# dispay.net
KiCad netlist of a schematic drawn in Altium Designer
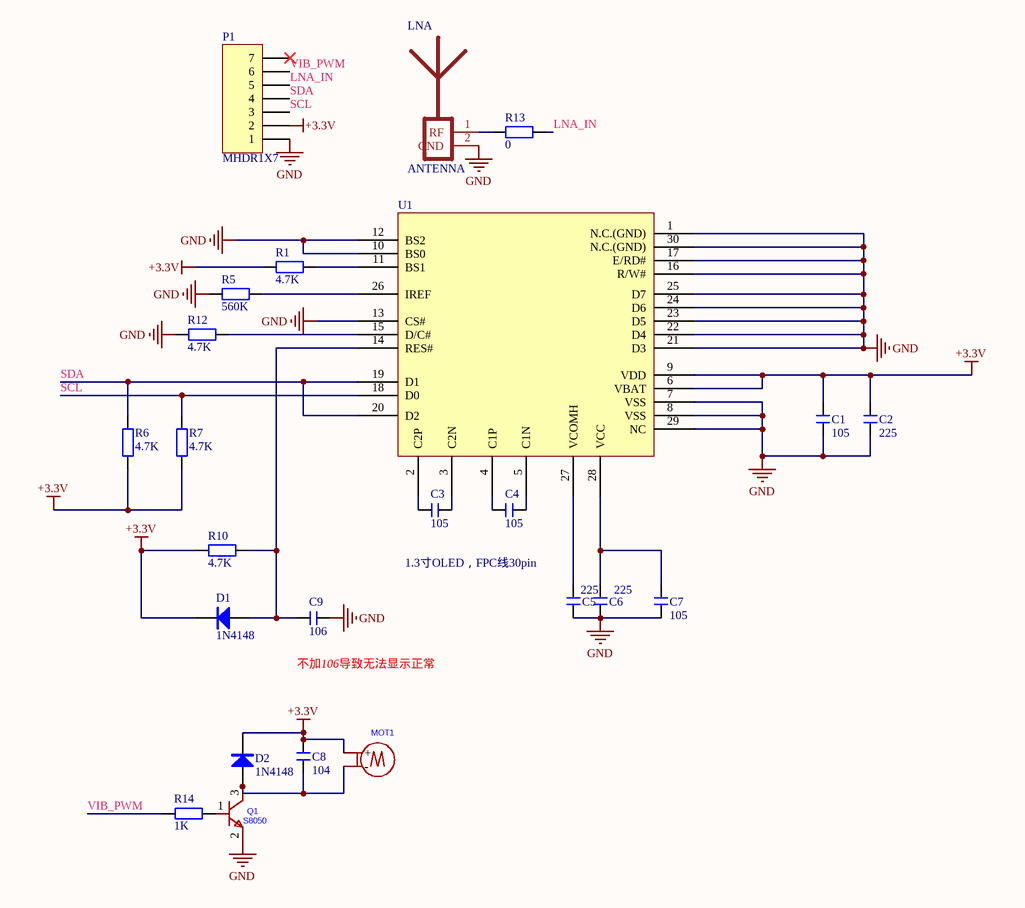
[diagram p0: dispay.SchDoc]

(export (version "E")
  (design (tool "Eeschema 10.0.6"))
  (components
    (comp (ref "C1")
      (value "105")
      (footprint "C0402-min")
      (description "无极性贴片电容")
      (fields (field (name "版权归属") "源创客"))
      (libsource (lib "3.1   - 电阻-电容-电感") (part "C"))
    )
    (comp (ref "C2")
      (value "225")
      (footprint "C0402-min")
      (description "无极性贴片电容")
      (fields (field (name "版权归属") "源创客"))
      (libsource (lib "3.1   - 电阻-电容-电感") (part "C"))
    )
    (comp (ref "C3")
      (value "105")
      (footprint "C0402-min")
      (description "无极性贴片电容")
      (fields (field (name "版权归属") "源创客"))
      (libsource (lib "3.1   - 电阻-电容-电感") (part "C"))
    )
    (comp (ref "C4")
      (value "105")
      (footprint "C0402-min")
      (description "无极性贴片电容")
      (fields (field (name "版权归属") "源创客"))
      (libsource (lib "3.1   - 电阻-电容-电感") (part "C"))
    )
    (comp (ref "C5")
      (value "225")
      (footprint "C0402-min")
      (description "无极性贴片电容")
      (fields (field (name "版权归属") "源创客"))
      (libsource (lib "3.1   - 电阻-电容-电感") (part "C"))
    )
    (comp (ref "C6")
      (value "225")
      (footprint "C0402-min")
      (description "无极性贴片电容")
      (fields (field (name "版权归属") "源创客"))
      (libsource (lib "3.1   - 电阻-电容-电感") (part "C"))
    )
    (comp (ref "C7")
      (value "105")
      (footprint "C0402-min")
      (description "无极性贴片电容")
      (fields (field (name "版权归属") "源创客"))
      (libsource (lib "3.1   - 电阻-电容-电感") (part "C"))
    )
    (comp (ref "C8")
      (value "104")
      (footprint "C0402-min")
      (description "无极性贴片电容")
      (fields (field (name "版权归属") "源创客"))
      (libsource (lib "3.1   - 电阻-电容-电感") (part "C"))
    )
    (comp (ref "C9")
      (value "106")
      (footprint "C0402-min")
      (description "无极性贴片电容")
      (fields (field (name "版权归属") "源创客"))
      (libsource (lib "3.1   - 电阻-电容-电感") (part "C"))
    )
    (comp (ref "D1")
      (value "1N4148")
      (footprint "SOD-323")
      (description "高速开关二极管")
      (fields (field (name "版权归属") "源创客"))
      (libsource (lib "8.1   - 二极管-整流桥") (part "1N4148"))
    )
    (comp (ref "D2")
      (value "1N4148")
      (footprint "SOD-323")
      (description "高速开关二极管")
      (fields (field (name "版权归属") "源创客"))
      (libsource (lib "8.1   - 二极管-整流桥") (part "1N4148"))
    )
    (comp (ref "LNA")
      (value "ANTENNA")
      (footprint "SWRA117D")
      (libsource (lib "Schlib-drive") (part "ANTENNA"))
    )
    (comp (ref "MOT1")
      (value "LCM1027A2445F")
      (footprint "Vibration_Motor0820")
      (fields (field (name "MANUFACTURER") "LEADER(立得)"))
      (libsource (lib "drive") (part "Vibration_Motor"))
    )
    (comp (ref "P1")
      (value "MHDR1X7")
      (footprint "MHDR1X7")
      (description "Header, 7-Pin")
      (fields (field (name "PUBLISHER") "Altium Limited"))
      (libsource (lib "Miscellaneous Connectors") (part "MHDR1X7"))
    )
    (comp (ref "Q1")
      (value "S8050")
      (footprint "SOT-23-3")
      (fields (field (name "MANUFACTURER") "宏嘉诚"))
      (libsource (lib "drive") (part "S8050"))
    )
    (comp (ref "R1")
      (value "4.7K")
      (footprint "R0402")
      (description "贴片电阻")
      (fields (field (name "版权归属") "源创客"))
      (libsource (lib "3.1   - 电阻-电容-电感") (part "R"))
    )
    (comp (ref "R5")
      (value "560K")
      (footprint "R0402")
      (description "贴片电阻")
      (fields (field (name "版权归属") "源创客"))
      (libsource (lib "3.1   - 电阻-电容-电感") (part "R"))
    )
    (comp (ref "R6")
      (value "4.7K")
      (footprint "R0402")
      (description "贴片电阻")
      (fields (field (name "版权归属") "源创客"))
      (libsource (lib "3.1   - 电阻-电容-电感") (part "R"))
    )
    (comp (ref "R7")
      (value "4.7K")
      (footprint "R0402")
      (description "贴片电阻")
      (fields (field (name "版权归属") "源创客"))
      (libsource (lib "3.1   - 电阻-电容-电感") (part "R"))
    )
    (comp (ref "R10")
      (value "4.7K")
      (footprint "R0402")
      (description "贴片电阻")
      (fields (field (name "版权归属") "源创客"))
      (libsource (lib "3.1   - 电阻-电容-电感") (part "R"))
    )
    (comp (ref "R12")
      (value "4.7K")
      (footprint "R0402")
      (description "贴片电阻")
      (fields (field (name "版权归属") "源创客"))
      (libsource (lib "3.1   - 电阻-电容-电感") (part "R"))
    )
    (comp (ref "R13")
      (value "0")
      (footprint "R0402")
      (description "贴片电阻")
      (fields (field (name "版权归属") "源创客"))
      (libsource (lib "3.1   - 电阻-电容-电感") (part "R"))
    )
    (comp (ref "R14")
      (value "1K")
      (footprint "R0402")
      (description "贴片电阻")
      (fields (field (name "版权归属") "源创客"))
      (libsource (lib "3.1   - 电阻-电容-电感") (part "R"))
    )
    (comp (ref "U1")
      (value "1.3寸OLED，FPC线30pin")
      (footprint "0.96OLED")
      (libsource (lib "我的元件") (part "1.3寸OLED，FPC线30pin"))
    )
  )
  (nets
    (net (code "1") (name "+3.3V") (class "Default")
      (node (ref "C1") (pin "2") (pinfunction "2_2") (pintype "passive"))
      (node (ref "C2") (pin "2") (pinfunction "2_2") (pintype "passive"))
      (node (ref "C8") (pin "2") (pinfunction "2_2") (pintype "passive"))
      (node (ref "D1") (pin "2") (pinfunction "K_2") (pintype "passive"))
      (node (ref "D2") (pin "2") (pinfunction "K_2") (pintype "passive"))
      (node (ref "MOT1") (pin "2") (pinfunction "+_2") (pintype "passive"))
      (node (ref "P1") (pin "2") (pinfunction "2_2") (pintype "passive"))
      (node (ref "R1") (pin "1") (pinfunction "1_1") (pintype "passive"))
      (node (ref "R10") (pin "1") (pinfunction "1_1") (pintype "passive"))
      (node (ref "R6") (pin "1") (pinfunction "1_1") (pintype "passive"))
      (node (ref "R7") (pin "1") (pinfunction "1_1") (pintype "passive"))
      (node (ref "U1") (pin "6") (pinfunction "VBAT_6") (pintype "passive"))
      (node (ref "U1") (pin "9") (pinfunction "VDD_9") (pintype "passive"))
    )
    (net (code "2") (name "/LNA_IN") (class "Default")
      (node (ref "P1") (pin "5") (pinfunction "5_5") (pintype "passive"))
      (node (ref "R13") (pin "2") (pinfunction "2_2") (pintype "passive"))
    )
    (net (code "3") (name "/SCL") (class "Default")
      (node (ref "P1") (pin "3") (pinfunction "3_3") (pintype "passive"))
      (node (ref "R7") (pin "2") (pinfunction "2_2") (pintype "passive"))
      (node (ref "U1") (pin "18") (pinfunction "D0_18") (pintype "passive"))
    )
    (net (code "4") (name "/SDA") (class "Default")
      (node (ref "P1") (pin "4") (pinfunction "4_4") (pintype "passive"))
      (node (ref "R6") (pin "2") (pinfunction "2_2") (pintype "passive"))
      (node (ref "U1") (pin "19") (pinfunction "D1_19") (pintype "passive"))
      (node (ref "U1") (pin "20") (pinfunction "D2_20") (pintype "passive"))
    )
    (net (code "5") (name "/VIB_PWM") (class "Default")
      (node (ref "P1") (pin "6") (pinfunction "6_6") (pintype "passive"))
      (node (ref "R14") (pin "1") (pinfunction "1_1") (pintype "passive"))
    )
    (net (code "6") (name "GND") (class "Default")
      (node (ref "C1") (pin "1") (pinfunction "1_1") (pintype "passive"))
      (node (ref "C2") (pin "1") (pinfunction "1_1") (pintype "passive"))
      (node (ref "C5") (pin "1") (pinfunction "1_1") (pintype "passive"))
      (node (ref "C6") (pin "1") (pinfunction "1_1") (pintype "passive"))
      (node (ref "C7") (pin "1") (pinfunction "1_1") (pintype "passive"))
      (node (ref "C9") (pin "2") (pinfunction "2_2") (pintype "passive"))
      (node (ref "LNA") (pin "2") (pinfunction "GND_2") (pintype "passive"))
      (node (ref "P1") (pin "1") (pinfunction "1_1") (pintype "passive"))
      (node (ref "Q1") (pin "2") (pinfunction "E_2") (pintype "passive"))
      (node (ref "R12") (pin "2") (pinfunction "2_2") (pintype "passive"))
      (node (ref "R5") (pin "1") (pinfunction "1_1") (pintype "passive"))
      (node (ref "U1") (pin "1") (pinfunction "N.C.(GND)_1") (pintype "passive"))
      (node (ref "U1") (pin "10") (pinfunction "BS0_10") (pintype "passive"))
      (node (ref "U1") (pin "12") (pinfunction "BS2_12") (pintype "passive"))
      (node (ref "U1") (pin "13") (pinfunction "CS#_13") (pintype "passive"))
      (node (ref "U1") (pin "16") (pinfunction "R/W#_16") (pintype "passive"))
      (node (ref "U1") (pin "17") (pinfunction "E/RD#_17") (pintype "passive"))
      (node (ref "U1") (pin "21") (pinfunction "D3_21") (pintype "passive"))
      (node (ref "U1") (pin "22") (pinfunction "D4_22") (pintype "passive"))
      (node (ref "U1") (pin "23") (pinfunction "D5_23") (pintype "passive"))
      (node (ref "U1") (pin "24") (pinfunction "D6_24") (pintype "passive"))
      (node (ref "U1") (pin "25") (pinfunction "D7_25") (pintype "passive"))
      (node (ref "U1") (pin "29") (pinfunction "NC_29") (pintype "passive"))
      (node (ref "U1") (pin "30") (pinfunction "N.C.(GND)_30") (pintype "passive"))
      (node (ref "U1") (pin "7") (pinfunction "VSS_7") (pintype "passive"))
      (node (ref "U1") (pin "8") (pinfunction "VSS_8") (pintype "passive"))
    )
    (net (code "7") (name "Net-(D1-A)") (class "Default")
      (node (ref "C9") (pin "1") (pinfunction "1_1") (pintype "passive"))
      (node (ref "D1") (pin "1") (pinfunction "A_1") (pintype "passive"))
      (node (ref "R10") (pin "2") (pinfunction "2_2") (pintype "passive"))
      (node (ref "U1") (pin "14") (pinfunction "RES#_14") (pintype "passive"))
    )
    (net (code "8") (name "Net-(D2-A)") (class "Default")
      (node (ref "C8") (pin "1") (pinfunction "1_1") (pintype "passive"))
      (node (ref "D2") (pin "1") (pinfunction "A_1") (pintype "passive"))
      (node (ref "MOT1") (pin "1") (pinfunction "-_1") (pintype "passive"))
      (node (ref "Q1") (pin "3") (pinfunction "C_3") (pintype "passive"))
    )
    (net (code "9") (name "Net-(LNA-RF)") (class "Default")
      (node (ref "LNA") (pin "1") (pinfunction "RF_1") (pintype "passive"))
      (node (ref "R13") (pin "1") (pinfunction "1_1") (pintype "passive"))
    )
    (net (code "10") (name "Net-(Q1-B)") (class "Default")
      (node (ref "Q1") (pin "1") (pinfunction "B_1") (pintype "passive"))
      (node (ref "R14") (pin "2") (pinfunction "2_2") (pintype "passive"))
    )
    (net (code "11") (name "Net-(U1-BS1)") (class "Default")
      (node (ref "R1") (pin "2") (pinfunction "2_2") (pintype "passive"))
      (node (ref "U1") (pin "11") (pinfunction "BS1_11") (pintype "passive"))
    )
    (net (code "12") (name "Net-(U1-C1N)") (class "Default")
      (node (ref "C4") (pin "2") (pinfunction "2_2") (pintype "passive"))
      (node (ref "U1") (pin "5") (pinfunction "C1N_5") (pintype "passive"))
    )
    (net (code "13") (name "Net-(U1-C1P)") (class "Default")
      (node (ref "C4") (pin "1") (pinfunction "1_1") (pintype "passive"))
      (node (ref "U1") (pin "4") (pinfunction "C1P_4") (pintype "passive"))
    )
    (net (code "14") (name "Net-(U1-C2N)") (class "Default")
      (node (ref "C3") (pin "2") (pinfunction "2_2") (pintype "passive"))
      (node (ref "U1") (pin "3") (pinfunction "C2N_3") (pintype "passive"))
    )
    (net (code "15") (name "Net-(U1-C2P)") (class "Default")
      (node (ref "C3") (pin "1") (pinfunction "1_1") (pintype "passive"))
      (node (ref "U1") (pin "2") (pinfunction "C2P_2") (pintype "passive"))
    )
    (net (code "16") (name "Net-(U1-D{slash}C#)") (class "Default")
      (node (ref "R12") (pin "1") (pinfunction "1_1") (pintype "passive"))
      (node (ref "U1") (pin "15") (pinfunction "D/C#_15") (pintype "passive"))
    )
    (net (code "17") (name "Net-(U1-IREF)") (class "Default")
      (node (ref "R5") (pin "2") (pinfunction "2_2") (pintype "passive"))
      (node (ref "U1") (pin "26") (pinfunction "IREF_26") (pintype "passive"))
    )
    (net (code "18") (name "Net-(U1-VCC)") (class "Default")
      (node (ref "C6") (pin "2") (pinfunction "2_2") (pintype "passive"))
      (node (ref "C7") (pin "2") (pinfunction "2_2") (pintype "passive"))
      (node (ref "U1") (pin "28") (pinfunction "VCC_28") (pintype "passive"))
    )
    (net (code "19") (name "Net-(U1-VCOMH)") (class "Default")
      (node (ref "C5") (pin "2") (pinfunction "2_2") (pintype "passive"))
      (node (ref "U1") (pin "27") (pinfunction "VCOMH_27") (pintype "passive"))
    )
    (net (code "20") (name "unconnected-(P1-Pad7)") (class "Default")
      (node (ref "P1") (pin "7") (pinfunction "7_7") (pintype "passive+no_connect"))
    )
  )
)
